# Directional_Coupler.net
KiCad netlist of a schematic drawn in Altium Designer
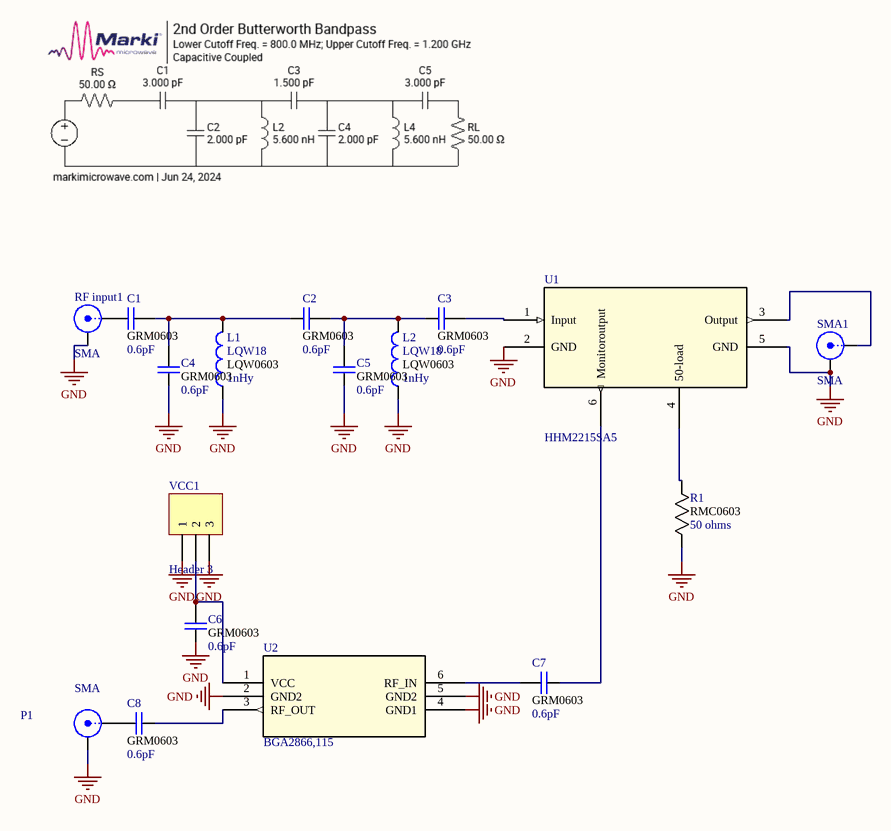
[diagram p0: Directional_Coupler.SchDoc]

(export (version "E")
  (design (tool "Eeschema 10.0.6"))
  (components
    (comp (ref "C1")
      (value "0.6pF")
      (footprint "GRM0603")
      (description "Capacitor GRM18 0603")
      (fields (field (name "Comment") "Cap 0603") (field (name "PUBLISHER") "Altium Limited"))
      (libsource (lib "Radar_RF_EAIII") (part "Cap"))
    )
    (comp (ref "C2")
      (value "0.6pF")
      (footprint "GRM0603")
      (description "Capacitor GRM18 0603")
      (fields (field (name "Comment") "Cap 0603") (field (name "PUBLISHER") "Altium Limited"))
      (libsource (lib "Radar_RF_EAIII") (part "Cap"))
    )
    (comp (ref "C3")
      (value "0.6pF")
      (footprint "GRM0603")
      (description "Capacitor GRM18 0603")
      (fields (field (name "Comment") "Cap 0603") (field (name "PUBLISHER") "Altium Limited"))
      (libsource (lib "Radar_RF_EAIII") (part "Cap"))
    )
    (comp (ref "C4")
      (value "0.6pF")
      (footprint "GRM0603")
      (description "Capacitor GRM18 0603")
      (fields (field (name "Comment") "Cap 0603") (field (name "PUBLISHER") "Altium Limited"))
      (libsource (lib "Radar_RF_EAIII") (part "Cap"))
    )
    (comp (ref "C5")
      (value "0.6pF")
      (footprint "GRM0603")
      (description "Capacitor GRM18 0603")
      (fields (field (name "Comment") "Cap 0603") (field (name "PUBLISHER") "Altium Limited"))
      (libsource (lib "Radar_RF_EAIII") (part "Cap"))
    )
    (comp (ref "C6")
      (value "0.6pF")
      (footprint "GRM0603")
      (description "Capacitor GRM18 0603")
      (fields (field (name "Comment") "Cap 0603") (field (name "PUBLISHER") "Altium Limited"))
      (libsource (lib "Radar_RF_EAIII") (part "Cap"))
    )
    (comp (ref "C7")
      (value "0.6pF")
      (footprint "GRM0603")
      (description "Capacitor GRM18 0603")
      (fields (field (name "Comment") "Cap 0603") (field (name "PUBLISHER") "Altium Limited"))
      (libsource (lib "Radar_RF_EAIII") (part "Cap"))
    )
    (comp (ref "C8")
      (value "0.6pF")
      (footprint "GRM0603")
      (description "Capacitor GRM18 0603")
      (fields (field (name "Comment") "Cap 0603") (field (name "PUBLISHER") "Altium Limited"))
      (libsource (lib "Radar_RF_EAIII") (part "Cap"))
    )
    (comp (ref "L1")
      (value "LQW18")
      (footprint "INDC1608X100N")
      (description "Ind RF Chip Wirewound 18nH 5% 100MHz 40Q-Factor 550mA 0603 Paper T/R")
      (fields
        (field (name "MP") "LQW18AN18NJ00D")
        (field (name "PARAMETER 1") "LQW0603")
        (field (name "ALTIUM_VALUE") "1nHy")
      )
      (libsource (lib "Radar_RF_EAIII") (part "LQW18"))
    )
    (comp (ref "L2")
      (value "LQW18")
      (footprint "INDC1608X100N")
      (description "Ind RF Chip Wirewound 18nH 5% 100MHz 40Q-Factor 550mA 0603 Paper T/R")
      (fields
        (field (name "MP") "LQW18AN18NJ00D")
        (field (name "PARAMETER 1") "LQW0603")
        (field (name "ALTIUM_VALUE") "1nHy")
      )
      (libsource (lib "Radar_RF_EAIII") (part "LQW18"))
    )
    (comp (ref "P1")
      (value "SMA")
      (footprint "SMA-142-0701-851_V2")
      (description "SMB Straight Connector")
      (fields (field (name "PUBLISHER") "Altium Limited"))
      (libsource (lib "PCB_Project") (part "SMB"))
    )
    (comp (ref "R1")
      (value "50 ohms")
      (footprint "RMC0603")
      (description "Resistor RMC0603")
      (fields (field (name "Comment") "Resistor"))
      (libsource (lib "Radar_RF_EAIII") (part "Resistor"))
    )
    (comp (ref "RF input1")
      (value "SMA")
      (footprint "SMA-142-0701-851_V2")
      (description "SMA Straight Connector")
      (fields (field (name "PUBLISHER") "Altium Limited"))
      (libsource (lib "Radar_RF_EAIII") (part "SMA"))
    )
    (comp (ref "SMA1")
      (value "SMA")
      (footprint "SMA-142-0701-851_V2")
      (description "SMA Straight Connector")
      (fields (field (name "PUBLISHER") "Altium Limited"))
      (libsource (lib "Radar_RF_EAIII") (part "SMA"))
    )
    (comp (ref "U1")
      (value "HHM2215SA5")
      (footprint "HHM-6_1P6X0P8")
      (description "No Description Available")
      (libsource (lib "Radar_RF_EAIII") (part "HHM2215SA5"))
    )
    (comp (ref "U2")
      (value "BGA2866,115")
      (footprint "SOT363_NXP")
      (description "No Description Available")
      (libsource (lib "Radar_RF_EAIII") (part "BGA2866,115"))
    )
    (comp (ref "VCC1")
      (value "Header 3")
      (footprint "HDR1X3")
      (description "Header, 3-Pin")
      (fields (field (name "PUBLISHER") "Altium Limited"))
      (libsource (lib "Miscellaneous Connectors") (part "Header 3"))
    )
  )
  (nets
    (net (code "1") (name "GND") (class "Default")
      (node (ref "C4") (pin "1") (pinfunction "1_1") (pintype "passive"))
      (node (ref "C5") (pin "1") (pinfunction "1_1") (pintype "passive"))
      (node (ref "C6") (pin "1") (pinfunction "1_1") (pintype "passive"))
      (node (ref "L1") (pin "1") (pinfunction "1_1") (pintype "passive"))
      (node (ref "L2") (pin "1") (pinfunction "1_1") (pintype "passive"))
      (node (ref "P1") (pin "2") (pinfunction "Y_2") (pintype "passive"))
      (node (ref "R1") (pin "1") (pinfunction "1_1") (pintype "passive"))
      (node (ref "RF input1") (pin "2") (pinfunction "Y_2") (pintype "passive"))
      (node (ref "SMA1") (pin "2") (pinfunction "Y_2") (pintype "passive"))
      (node (ref "U1") (pin "2") (pinfunction "GND_2") (pintype "power_in"))
      (node (ref "U1") (pin "5") (pinfunction "GND_5") (pintype "power_in"))
      (node (ref "U2") (pin "2") (pinfunction "GND2_2") (pintype "power_in"))
      (node (ref "U2") (pin "4") (pinfunction "GND1_4") (pintype "power_in"))
      (node (ref "U2") (pin "5") (pinfunction "GND2_5") (pintype "power_in"))
      (node (ref "VCC1") (pin "1") (pinfunction "1_1") (pintype "passive"))
      (node (ref "VCC1") (pin "3") (pinfunction "3_3") (pintype "passive"))
    )
    (net (code "2") (name "Net-(C1-Pad2)") (class "Default")
      (node (ref "C1") (pin "2") (pinfunction "2_2") (pintype "passive"))
      (node (ref "C2") (pin "1") (pinfunction "1_1") (pintype "passive"))
      (node (ref "C4") (pin "2") (pinfunction "2_2") (pintype "passive"))
      (node (ref "L1") (pin "2") (pinfunction "2_2") (pintype "passive"))
    )
    (net (code "3") (name "Net-(C2-Pad2)") (class "Default")
      (node (ref "C2") (pin "2") (pinfunction "2_2") (pintype "passive"))
      (node (ref "C3") (pin "1") (pinfunction "1_1") (pintype "passive"))
      (node (ref "C5") (pin "2") (pinfunction "2_2") (pintype "passive"))
      (node (ref "L2") (pin "2") (pinfunction "2_2") (pintype "passive"))
    )
    (net (code "4") (name "Net-(P1-X)") (class "Default")
      (node (ref "C8") (pin "2") (pinfunction "2_2") (pintype "passive"))
      (node (ref "P1") (pin "1") (pinfunction "X_1") (pintype "passive"))
    )
    (net (code "5") (name "Net-(RF input1-X)") (class "Default")
      (node (ref "C1") (pin "1") (pinfunction "1_1") (pintype "passive"))
      (node (ref "RF input1") (pin "1") (pinfunction "X_1") (pintype "passive"))
    )
    (net (code "6") (name "Net-(SMA1-X)") (class "Default")
      (node (ref "SMA1") (pin "1") (pinfunction "X_1") (pintype "passive"))
      (node (ref "U1") (pin "3") (pinfunction "Output_3") (pintype "output"))
    )
    (net (code "7") (name "Net-(U1-50-load)") (class "Default")
      (node (ref "R1") (pin "2") (pinfunction "2_2") (pintype "passive"))
      (node (ref "U1") (pin "4") (pinfunction "50-load_4") (pintype "passive"))
    )
    (net (code "8") (name "Net-(U1-Input)") (class "Default")
      (node (ref "C3") (pin "2") (pinfunction "2_2") (pintype "passive"))
      (node (ref "U1") (pin "1") (pinfunction "Input_1") (pintype "input"))
    )
    (net (code "9") (name "Net-(U1-Monitoroutput)") (class "Default")
      (node (ref "C7") (pin "1") (pinfunction "1_1") (pintype "passive"))
      (node (ref "U1") (pin "6") (pinfunction "Monitoroutput_6") (pintype "output"))
    )
    (net (code "10") (name "Net-(U2-RF_IN)") (class "Default")
      (node (ref "C7") (pin "2") (pinfunction "2_2") (pintype "passive"))
      (node (ref "U2") (pin "6") (pinfunction "RF_IN_6") (pintype "passive"))
    )
    (net (code "11") (name "Net-(U2-RF_OUT)") (class "Default")
      (node (ref "C8") (pin "1") (pinfunction "1_1") (pintype "passive"))
      (node (ref "U2") (pin "3") (pinfunction "RF_OUT_3") (pintype "output"))
    )
    (net (code "12") (name "Net-(U2-VCC)") (class "Default")
      (node (ref "C6") (pin "2") (pinfunction "2_2") (pintype "passive"))
      (node (ref "U2") (pin "1") (pinfunction "VCC_1") (pintype "power_in"))
      (node (ref "VCC1") (pin "2") (pinfunction "2_2") (pintype "passive"))
    )
  )
)
